# Auto_Final_v2_0.net
KiCad netlist of a schematic drawn in EAGLE
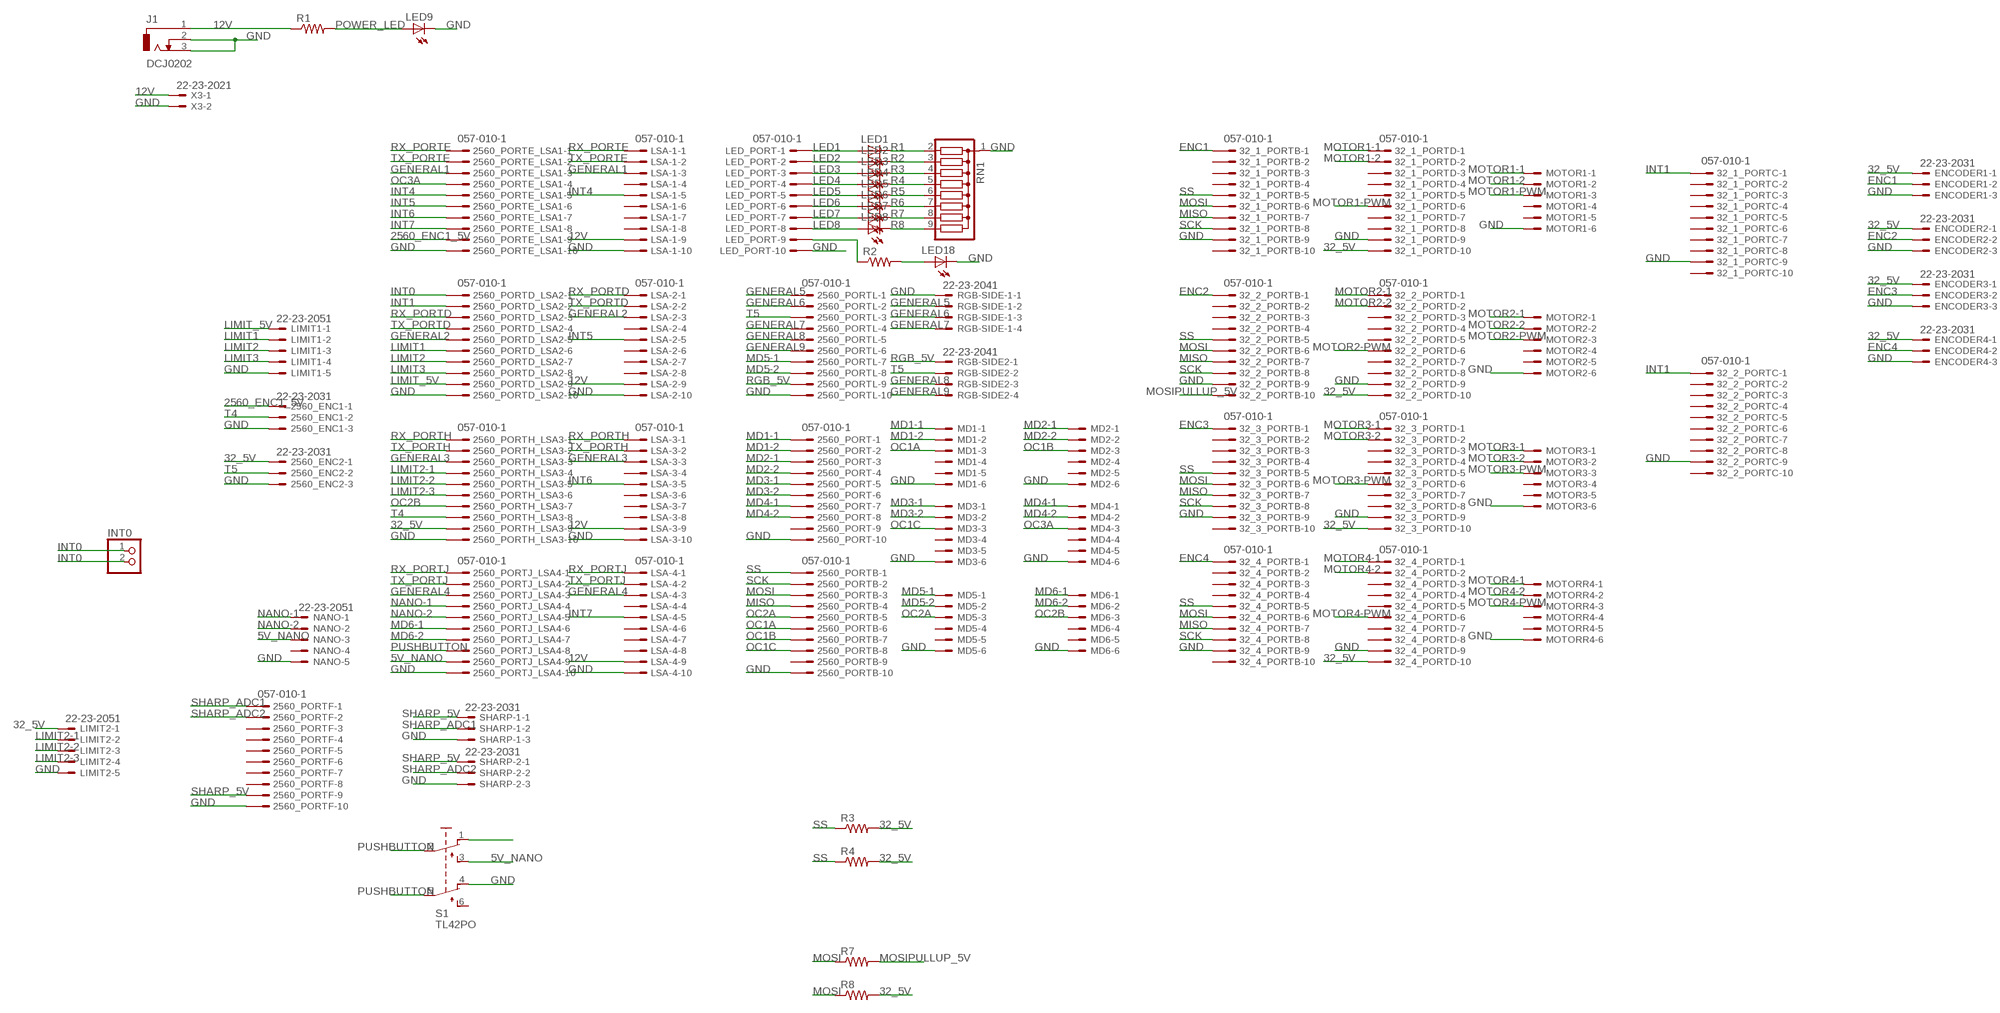
[diagram p0: schematic, sheet 1]

(export (version "E")
  (design (tool "Eeschema 10.0.6"))
  (components
    (comp (ref "32_1_PORTB")
      (value "057-010-1")
      (footprint "eagle-import:057-010-1")
      (libsource (lib "eagle-import") (part "057-010-1"))
    )
    (comp (ref "32_1_PORTC")
      (value "057-010-1")
      (footprint "eagle-import:057-010-1")
      (libsource (lib "eagle-import") (part "057-010-1"))
    )
    (comp (ref "32_1_PORTD")
      (value "057-010-1")
      (footprint "eagle-import:057-010-1")
      (libsource (lib "eagle-import") (part "057-010-1"))
    )
    (comp (ref "32_2_PORTB")
      (value "057-010-1")
      (footprint "eagle-import:057-010-1")
      (libsource (lib "eagle-import") (part "057-010-1"))
    )
    (comp (ref "32_2_PORTC")
      (value "057-010-1")
      (footprint "eagle-import:057-010-1")
      (libsource (lib "eagle-import") (part "057-010-1"))
    )
    (comp (ref "32_2_PORTD")
      (value "057-010-1")
      (footprint "eagle-import:057-010-1")
      (libsource (lib "eagle-import") (part "057-010-1"))
    )
    (comp (ref "32_3_PORTB")
      (value "057-010-1")
      (footprint "eagle-import:057-010-1")
      (libsource (lib "eagle-import") (part "057-010-1"))
    )
    (comp (ref "32_3_PORTD")
      (value "057-010-1")
      (footprint "eagle-import:057-010-1")
      (libsource (lib "eagle-import") (part "057-010-1"))
    )
    (comp (ref "32_4_PORTB")
      (value "057-010-1")
      (footprint "eagle-import:057-010-1")
      (libsource (lib "eagle-import") (part "057-010-1"))
    )
    (comp (ref "32_4_PORTD")
      (value "057-010-1")
      (footprint "eagle-import:057-010-1")
      (libsource (lib "eagle-import") (part "057-010-1"))
    )
    (comp (ref "2560_ENC1")
      (value "22-23-2031")
      (footprint "eagle-import:22-23-2031")
      (fields (field (name "MF") "MOLEX"))
      (libsource (lib "eagle-import") (part "22-23-2031"))
    )
    (comp (ref "2560_ENC2")
      (value "22-23-2031")
      (footprint "eagle-import:22-23-2031")
      (fields (field (name "MF") "MOLEX"))
      (libsource (lib "eagle-import") (part "22-23-2031"))
    )
    (comp (ref "2560_PORT")
      (value "057-010-1")
      (footprint "eagle-import:057-010-1")
      (libsource (lib "eagle-import") (part "057-010-1"))
    )
    (comp (ref "2560_PORTB")
      (value "057-010-1")
      (footprint "eagle-import:057-010-1")
      (libsource (lib "eagle-import") (part "057-010-1"))
    )
    (comp (ref "2560_PORTD_LSA2")
      (value "057-010-1")
      (footprint "eagle-import:057-010-1")
      (libsource (lib "eagle-import") (part "057-010-1"))
    )
    (comp (ref "2560_PORTE_LSA1")
      (value "057-010-1")
      (footprint "eagle-import:057-010-1")
      (libsource (lib "eagle-import") (part "057-010-1"))
    )
    (comp (ref "2560_PORTF")
      (value "057-010-1")
      (footprint "eagle-import:057-010-1")
      (libsource (lib "eagle-import") (part "057-010-1"))
    )
    (comp (ref "2560_PORTH_LSA3")
      (value "057-010-1")
      (footprint "eagle-import:057-010-1")
      (libsource (lib "eagle-import") (part "057-010-1"))
    )
    (comp (ref "2560_PORTJ_LSA4")
      (value "057-010-1")
      (footprint "eagle-import:057-010-1")
      (libsource (lib "eagle-import") (part "057-010-1"))
    )
    (comp (ref "2560_PORTL")
      (value "057-010-1")
      (footprint "eagle-import:057-010-1")
      (libsource (lib "eagle-import") (part "057-010-1"))
    )
    (comp (ref "ENCODER1")
      (value "22-23-2031")
      (footprint "eagle-import:22-23-2031")
      (fields (field (name "MF") "MOLEX"))
      (libsource (lib "eagle-import") (part "22-23-2031"))
    )
    (comp (ref "ENCODER2")
      (value "22-23-2031")
      (footprint "eagle-import:22-23-2031")
      (fields (field (name "MF") "MOLEX"))
      (libsource (lib "eagle-import") (part "22-23-2031"))
    )
    (comp (ref "ENCODER3")
      (value "22-23-2031")
      (footprint "eagle-import:22-23-2031")
      (fields (field (name "MF") "MOLEX"))
      (libsource (lib "eagle-import") (part "22-23-2031"))
    )
    (comp (ref "ENCODER4")
      (value "22-23-2031")
      (footprint "eagle-import:22-23-2031")
      (fields (field (name "MF") "MOLEX"))
      (libsource (lib "eagle-import") (part "22-23-2031"))
    )
    (comp (ref "INT0")
      (value "PINHD-1X2")
      (footprint "eagle-import:1X02")
      (libsource (lib "eagle-import") (part "PINHD-1X2"))
    )
    (comp (ref "J1")
      (value "DCJ0202")
      (footprint "eagle-import:DCJ0202")
      (libsource (lib "eagle-import") (part "DCJ0202"))
    )
    (comp (ref "LED1")
      (value "LED3MM")
      (footprint "eagle-import:LED3MM")
      (libsource (lib "eagle-import") (part "LED3MM"))
    )
    (comp (ref "LED2")
      (value "LED3MM")
      (footprint "eagle-import:LED3MM")
      (libsource (lib "eagle-import") (part "LED3MM"))
    )
    (comp (ref "LED3")
      (value "LED3MM")
      (footprint "eagle-import:LED3MM")
      (libsource (lib "eagle-import") (part "LED3MM"))
    )
    (comp (ref "LED4")
      (value "LED3MM")
      (footprint "eagle-import:LED3MM")
      (libsource (lib "eagle-import") (part "LED3MM"))
    )
    (comp (ref "LED5")
      (value "LED3MM")
      (footprint "eagle-import:LED3MM")
      (libsource (lib "eagle-import") (part "LED3MM"))
    )
    (comp (ref "LED6")
      (value "LED3MM")
      (footprint "eagle-import:LED3MM")
      (libsource (lib "eagle-import") (part "LED3MM"))
    )
    (comp (ref "LED7")
      (value "LED3MM")
      (footprint "eagle-import:LED3MM")
      (libsource (lib "eagle-import") (part "LED3MM"))
    )
    (comp (ref "LED8")
      (value "LED3MM")
      (footprint "eagle-import:LED3MM")
      (libsource (lib "eagle-import") (part "LED3MM"))
    )
    (comp (ref "LED9")
      (value "LED5MM")
      (footprint "eagle-import:LED5MM")
      (libsource (lib "eagle-import") (part "LED5MM"))
    )
    (comp (ref "LED18")
      (value "LED3MM")
      (footprint "eagle-import:LED3MM")
      (libsource (lib "eagle-import") (part "LED3MM"))
    )
    (comp (ref "LED_PORT")
      (value "057-010-1")
      (footprint "eagle-import:057-010-1")
      (libsource (lib "eagle-import") (part "057-010-1"))
    )
    (comp (ref "LIMIT1")
      (value "22-23-2051")
      (footprint "eagle-import:22-23-2051")
      (fields (field (name "MF") "MOLEX"))
      (libsource (lib "eagle-import") (part "22-23-2051"))
    )
    (comp (ref "LIMIT2")
      (value "22-23-2051")
      (footprint "eagle-import:22-23-2051")
      (fields (field (name "MF") "MOLEX"))
      (libsource (lib "eagle-import") (part "22-23-2051"))
    )
    (comp (ref "LSA-1")
      (value "057-010-1")
      (footprint "eagle-import:057-010-1")
      (libsource (lib "eagle-import") (part "057-010-1"))
    )
    (comp (ref "LSA-2")
      (value "057-010-1")
      (footprint "eagle-import:057-010-1")
      (libsource (lib "eagle-import") (part "057-010-1"))
    )
    (comp (ref "LSA-3")
      (value "057-010-1")
      (footprint "eagle-import:057-010-1")
      (libsource (lib "eagle-import") (part "057-010-1"))
    )
    (comp (ref "LSA-4")
      (value "057-010-1")
      (footprint "eagle-import:057-010-1")
      (libsource (lib "eagle-import") (part "057-010-1"))
    )
    (comp (ref "MD1")
      (value "22-23-2061")
      (footprint "eagle-import:22-23-2061")
      (fields (field (name "MF") "MOLEX"))
      (libsource (lib "eagle-import") (part "22-23-2061"))
    )
    (comp (ref "MD2")
      (value "22-23-2061")
      (footprint "eagle-import:22-23-2061")
      (fields (field (name "MF") "MOLEX"))
      (libsource (lib "eagle-import") (part "22-23-2061"))
    )
    (comp (ref "MD3")
      (value "22-23-2061")
      (footprint "eagle-import:22-23-2061")
      (fields (field (name "MF") "MOLEX"))
      (libsource (lib "eagle-import") (part "22-23-2061"))
    )
    (comp (ref "MD4")
      (value "22-23-2061")
      (footprint "eagle-import:22-23-2061")
      (fields (field (name "MF") "MOLEX"))
      (libsource (lib "eagle-import") (part "22-23-2061"))
    )
    (comp (ref "MD5")
      (value "22-23-2061")
      (footprint "eagle-import:22-23-2061")
      (fields (field (name "MF") "MOLEX"))
      (libsource (lib "eagle-import") (part "22-23-2061"))
    )
    (comp (ref "MD6")
      (value "22-23-2061")
      (footprint "eagle-import:22-23-2061")
      (fields (field (name "MF") "MOLEX"))
      (libsource (lib "eagle-import") (part "22-23-2061"))
    )
    (comp (ref "MOTOR1")
      (value "22-23-2061")
      (footprint "eagle-import:22-23-2061")
      (fields (field (name "MF") "MOLEX"))
      (libsource (lib "eagle-import") (part "22-23-2061"))
    )
    (comp (ref "MOTOR2")
      (value "22-23-2061")
      (footprint "eagle-import:22-23-2061")
      (fields (field (name "MF") "MOLEX"))
      (libsource (lib "eagle-import") (part "22-23-2061"))
    )
    (comp (ref "MOTOR3")
      (value "22-23-2061")
      (footprint "eagle-import:22-23-2061")
      (fields (field (name "MF") "MOLEX"))
      (libsource (lib "eagle-import") (part "22-23-2061"))
    )
    (comp (ref "MOTORR4")
      (value "22-23-2061")
      (footprint "eagle-import:22-23-2061")
      (fields (field (name "MF") "MOLEX"))
      (libsource (lib "eagle-import") (part "22-23-2061"))
    )
    (comp (ref "NANO")
      (value "22-23-2051")
      (footprint "eagle-import:22-23-2051")
      (fields (field (name "MF") "MOLEX"))
      (libsource (lib "eagle-import") (part "22-23-2051"))
    )
    (comp (ref "R1")
      (value "R-US_0204/7")
      (footprint "eagle-import:0204_7")
      (libsource (lib "eagle-import") (part "R-US_0204/7"))
    )
    (comp (ref "R2")
      (value "R-US_0204/7")
      (footprint "eagle-import:0204_7")
      (libsource (lib "eagle-import") (part "R-US_0204/7"))
    )
    (comp (ref "R3")
      (value "R-US_0204/7")
      (footprint "eagle-import:0204_7")
      (libsource (lib "eagle-import") (part "R-US_0204/7"))
    )
    (comp (ref "R4")
      (value "R-US_0204/7")
      (footprint "eagle-import:0204_7")
      (libsource (lib "eagle-import") (part "R-US_0204/7"))
    )
    (comp (ref "R7")
      (value "R-US_0204/7")
      (footprint "eagle-import:0204_7")
      (libsource (lib "eagle-import") (part "R-US_0204/7"))
    )
    (comp (ref "R8")
      (value "R-US_0204/7")
      (footprint "eagle-import:0204_7")
      (libsource (lib "eagle-import") (part "R-US_0204/7"))
    )
    (comp (ref "RGB-SIDE-1")
      (value "22-23-2041")
      (footprint "eagle-import:22-23-2041")
      (fields (field (name "MF") "MOLEX"))
      (libsource (lib "eagle-import") (part "22-23-2041"))
    )
    (comp (ref "RGB-SIDE2")
      (value "22-23-2041")
      (footprint "eagle-import:22-23-2041")
      (fields (field (name "MF") "MOLEX"))
      (libsource (lib "eagle-import") (part "22-23-2041"))
    )
    (comp (ref "RN1")
      (value "G08R")
      (footprint "eagle-import:SIL9")
      (libsource (lib "eagle-import") (part "G08R"))
    )
    (comp (ref "S1")
      (value "TL42PO")
      (footprint "eagle-import:TL4XPO")
      (libsource (lib "eagle-import") (part "TL42PO"))
    )
    (comp (ref "SHARP-1")
      (value "22-23-2031")
      (footprint "eagle-import:22-23-2031")
      (fields (field (name "MF") "MOLEX"))
      (libsource (lib "eagle-import") (part "22-23-2031"))
    )
    (comp (ref "SHARP-2")
      (value "22-23-2031")
      (footprint "eagle-import:22-23-2031")
      (fields (field (name "MF") "MOLEX"))
      (libsource (lib "eagle-import") (part "22-23-2031"))
    )
    (comp (ref "X3")
      (value "22-23-2021")
      (footprint "eagle-import:22-23-2021")
      (fields (field (name "MF") "MOLEX"))
      (libsource (lib "eagle-import") (part "22-23-2021"))
    )
  )
  (nets
    (net (code "1") (name "/5V_NANO") (class "Default")
      (node (ref "2560_PORTJ_LSA4") (pin "9") (pinfunction "S_9") (pintype "passive"))
      (node (ref "NANO") (pin "3") (pinfunction "S_3") (pintype "passive"))
      (node (ref "S1") (pin "3") (pinfunction "S_3") (pintype "passive"))
    )
    (net (code "2") (name "/12V") (class "Default")
      (node (ref "J1") (pin "1") (pinfunction "1_1") (pintype "passive"))
      (node (ref "LSA-1") (pin "9") (pinfunction "S_9") (pintype "passive"))
      (node (ref "LSA-2") (pin "9") (pinfunction "S_9") (pintype "passive"))
      (node (ref "LSA-3") (pin "9") (pinfunction "S_9") (pintype "passive"))
      (node (ref "LSA-4") (pin "9") (pinfunction "S_9") (pintype "passive"))
      (node (ref "R1") (pin "1") (pinfunction "1_1") (pintype "passive"))
      (node (ref "X3") (pin "1") (pinfunction "S_1") (pintype "passive"))
    )
    (net (code "3") (name "/32_5V") (class "Default")
      (node (ref "2560_ENC2") (pin "1") (pinfunction "S_1") (pintype "passive"))
      (node (ref "2560_PORTH_LSA3") (pin "9") (pinfunction "S_9") (pintype "passive"))
      (node (ref "32_1_PORTD") (pin "10") (pinfunction "S_10") (pintype "passive"))
      (node (ref "32_2_PORTD") (pin "10") (pinfunction "S_10") (pintype "passive"))
      (node (ref "32_3_PORTD") (pin "10") (pinfunction "S_10") (pintype "passive"))
      (node (ref "32_4_PORTD") (pin "10") (pinfunction "S_10") (pintype "passive"))
      (node (ref "ENCODER1") (pin "1") (pinfunction "S_1") (pintype "passive"))
      (node (ref "ENCODER2") (pin "1") (pinfunction "S_1") (pintype "passive"))
      (node (ref "ENCODER3") (pin "1") (pinfunction "S_1") (pintype "passive"))
      (node (ref "ENCODER4") (pin "1") (pinfunction "S_1") (pintype "passive"))
      (node (ref "LIMIT2") (pin "1") (pinfunction "S_1") (pintype "passive"))
      (node (ref "R3") (pin "2") (pinfunction "2_2") (pintype "passive"))
      (node (ref "R4") (pin "2") (pinfunction "2_2") (pintype "passive"))
      (node (ref "R8") (pin "2") (pinfunction "2_2") (pintype "passive"))
    )
    (net (code "4") (name "/2560_ENC1_5V") (class "Default")
      (node (ref "2560_ENC1") (pin "1") (pinfunction "S_1") (pintype "passive"))
      (node (ref "2560_PORTE_LSA1") (pin "9") (pinfunction "S_9") (pintype "passive"))
    )
    (net (code "5") (name "/ENC1") (class "Default")
      (node (ref "32_1_PORTB") (pin "1") (pinfunction "S_1") (pintype "passive"))
      (node (ref "ENCODER1") (pin "2") (pinfunction "S_2") (pintype "passive"))
    )
    (net (code "6") (name "/ENC2") (class "Default")
      (node (ref "32_2_PORTB") (pin "1") (pinfunction "S_1") (pintype "passive"))
      (node (ref "ENCODER2") (pin "2") (pinfunction "S_2") (pintype "passive"))
    )
    (net (code "7") (name "/ENC3") (class "Default")
      (node (ref "32_3_PORTB") (pin "1") (pinfunction "S_1") (pintype "passive"))
      (node (ref "ENCODER3") (pin "2") (pinfunction "S_2") (pintype "passive"))
    )
    (net (code "8") (name "/ENC4") (class "Default")
      (node (ref "32_4_PORTB") (pin "1") (pinfunction "S_1") (pintype "passive"))
      (node (ref "ENCODER4") (pin "2") (pinfunction "S_2") (pintype "passive"))
    )
    (net (code "9") (name "/GENERAL1") (class "Default")
      (node (ref "2560_PORTE_LSA1") (pin "3") (pinfunction "S_3") (pintype "passive"))
      (node (ref "LSA-1") (pin "3") (pinfunction "S_3") (pintype "passive"))
    )
    (net (code "10") (name "/GENERAL2") (class "Default")
      (node (ref "2560_PORTD_LSA2") (pin "5") (pinfunction "S_5") (pintype "passive"))
      (node (ref "LSA-2") (pin "3") (pinfunction "S_3") (pintype "passive"))
    )
    (net (code "11") (name "/GENERAL3") (class "Default")
      (node (ref "2560_PORTH_LSA3") (pin "3") (pinfunction "S_3") (pintype "passive"))
      (node (ref "LSA-3") (pin "3") (pinfunction "S_3") (pintype "passive"))
    )
    (net (code "12") (name "/GENERAL4") (class "Default")
      (node (ref "2560_PORTJ_LSA4") (pin "3") (pinfunction "S_3") (pintype "passive"))
      (node (ref "LSA-4") (pin "3") (pinfunction "S_3") (pintype "passive"))
    )
    (net (code "13") (name "/GENERAL5") (class "Default")
      (node (ref "2560_PORTL") (pin "1") (pinfunction "S_1") (pintype "passive"))
      (node (ref "RGB-SIDE-1") (pin "2") (pinfunction "S_2") (pintype "passive"))
    )
    (net (code "14") (name "/GENERAL6") (class "Default")
      (node (ref "2560_PORTL") (pin "2") (pinfunction "S_2") (pintype "passive"))
      (node (ref "RGB-SIDE-1") (pin "3") (pinfunction "S_3") (pintype "passive"))
    )
    (net (code "15") (name "/GENERAL7") (class "Default")
      (node (ref "2560_PORTL") (pin "4") (pinfunction "S_4") (pintype "passive"))
      (node (ref "RGB-SIDE-1") (pin "4") (pinfunction "S_4") (pintype "passive"))
    )
    (net (code "16") (name "/GENERAL8") (class "Default")
      (node (ref "2560_PORTL") (pin "5") (pinfunction "S_5") (pintype "passive"))
      (node (ref "RGB-SIDE2") (pin "3") (pinfunction "S_3") (pintype "passive"))
    )
    (net (code "17") (name "/GENERAL9") (class "Default")
      (node (ref "2560_PORTL") (pin "6") (pinfunction "S_6") (pintype "passive"))
      (node (ref "RGB-SIDE2") (pin "4") (pinfunction "S_4") (pintype "passive"))
    )
    (net (code "18") (name "/GND") (class "Default")
      (node (ref "2560_ENC1") (pin "3") (pinfunction "S_3") (pintype "passive"))
      (node (ref "2560_ENC2") (pin "3") (pinfunction "S_3") (pintype "passive"))
      (node (ref "2560_PORT") (pin "10") (pinfunction "S_10") (pintype "passive"))
      (node (ref "2560_PORTB") (pin "10") (pinfunction "S_10") (pintype "passive"))
      (node (ref "2560_PORTD_LSA2") (pin "10") (pinfunction "S_10") (pintype "passive"))
      (node (ref "2560_PORTE_LSA1") (pin "10") (pinfunction "S_10") (pintype "passive"))
      (node (ref "2560_PORTF") (pin "10") (pinfunction "S_10") (pintype "passive"))
      (node (ref "2560_PORTH_LSA3") (pin "10") (pinfunction "S_10") (pintype "passive"))
      (node (ref "2560_PORTJ_LSA4") (pin "10") (pinfunction "S_10") (pintype "passive"))
      (node (ref "2560_PORTL") (pin "10") (pinfunction "S_10") (pintype "passive"))
      (node (ref "32_1_PORTB") (pin "9") (pinfunction "S_9") (pintype "passive"))
      (node (ref "32_1_PORTC") (pin "9") (pinfunction "S_9") (pintype "passive"))
      (node (ref "32_1_PORTD") (pin "9") (pinfunction "S_9") (pintype "passive"))
      (node (ref "32_2_PORTB") (pin "9") (pinfunction "S_9") (pintype "passive"))
      (node (ref "32_2_PORTC") (pin "9") (pinfunction "S_9") (pintype "passive"))
      (node (ref "32_2_PORTD") (pin "9") (pinfunction "S_9") (pintype "passive"))
      (node (ref "32_3_PORTB") (pin "9") (pinfunction "S_9") (pintype "passive"))
      (node (ref "32_3_PORTD") (pin "9") (pinfunction "S_9") (pintype "passive"))
      (node (ref "32_4_PORTB") (pin "9") (pinfunction "S_9") (pintype "passive"))
      (node (ref "32_4_PORTD") (pin "9") (pinfunction "S_9") (pintype "passive"))
      (node (ref "ENCODER1") (pin "3") (pinfunction "S_3") (pintype "passive"))
      (node (ref "ENCODER2") (pin "3") (pinfunction "S_3") (pintype "passive"))
      (node (ref "ENCODER3") (pin "3") (pinfunction "S_3") (pintype "passive"))
      (node (ref "ENCODER4") (pin "3") (pinfunction "S_3") (pintype "passive"))
      (node (ref "J1") (pin "2") (pinfunction "2_2") (pintype "passive"))
      (node (ref "J1") (pin "3") (pinfunction "3_3") (pintype "passive"))
      (node (ref "LED18") (pin "K") (pinfunction "C_K") (pintype "passive"))
      (node (ref "LED9") (pin "K") (pinfunction "C_K") (pintype "passive"))
      (node (ref "LED_PORT") (pin "10") (pinfunction "S_10") (pintype "passive"))
      (node (ref "LIMIT1") (pin "5") (pinfunction "S_5") (pintype "passive"))
      (node (ref "LIMIT2") (pin "5") (pinfunction "S_5") (pintype "passive"))
      (node (ref "LSA-1") (pin "10") (pinfunction "S_10") (pintype "passive"))
      (node (ref "LSA-2") (pin "10") (pinfunction "S_10") (pintype "passive"))
      (node (ref "LSA-3") (pin "10") (pinfunction "S_10") (pintype "passive"))
      (node (ref "LSA-4") (pin "10") (pinfunction "S_10") (pintype "passive"))
      (node (ref "MD1") (pin "6") (pinfunction "S_6") (pintype "passive"))
      (node (ref "MD2") (pin "6") (pinfunction "S_6") (pintype "passive"))
      (node (ref "MD3") (pin "6") (pinfunction "S_6") (pintype "passive"))
      (node (ref "MD4") (pin "6") (pinfunction "S_6") (pintype "passive"))
      (node (ref "MD5") (pin "6") (pinfunction "S_6") (pintype "passive"))
      (node (ref "MD6") (pin "6") (pinfunction "S_6") (pintype "passive"))
      (node (ref "MOTOR1") (pin "6") (pinfunction "S_6") (pintype "passive"))
      (node (ref "MOTOR2") (pin "6") (pinfunction "S_6") (pintype "passive"))
      (node (ref "MOTOR3") (pin "6") (pinfunction "S_6") (pintype "passive"))
      (node (ref "MOTORR4") (pin "6") (pinfunction "S_6") (pintype "passive"))
      (node (ref "NANO") (pin "5") (pinfunction "S_5") (pintype "passive"))
      (node (ref "RGB-SIDE-1") (pin "1") (pinfunction "S_1") (pintype "passive"))
      (node (ref "RN1") (pin "1") (pinfunction "1_1") (pintype "passive"))
      (node (ref "S1") (pin "4") (pinfunction "O1_4") (pintype "passive"))
      (node (ref "SHARP-1") (pin "3") (pinfunction "S_3") (pintype "passive"))
      (node (ref "SHARP-2") (pin "3") (pinfunction "S_3") (pintype "passive"))
      (node (ref "X3") (pin "2") (pinfunction "S_2") (pintype "passive"))
    )
    (net (code "19") (name "/INT0") (class "Default")
      (node (ref "2560_PORTD_LSA2") (pin "1") (pinfunction "S_1") (pintype "passive"))
      (node (ref "INT0") (pin "1") (pinfunction "1_1") (pintype "passive"))
      (node (ref "INT0") (pin "2") (pinfunction "2_2") (pintype "passive"))
    )
    (net (code "20") (name "/INT1") (class "Default")
      (node (ref "2560_PORTD_LSA2") (pin "2") (pinfunction "S_2") (pintype "passive"))
      (node (ref "32_1_PORTC") (pin "1") (pinfunction "S_1") (pintype "passive"))
      (node (ref "32_2_PORTC") (pin "1") (pinfunction "S_1") (pintype "passive"))
    )
    (net (code "21") (name "/INT4") (class "Default")
      (node (ref "2560_PORTE_LSA1") (pin "5") (pinfunction "S_5") (pintype "passive"))
      (node (ref "LSA-1") (pin "5") (pinfunction "S_5") (pintype "passive"))
    )
    (net (code "22") (name "/INT5") (class "Default")
      (node (ref "2560_PORTE_LSA1") (pin "6") (pinfunction "S_6") (pintype "passive"))
      (node (ref "LSA-2") (pin "5") (pinfunction "S_5") (pintype "passive"))
    )
    (net (code "23") (name "/INT6") (class "Default")
      (node (ref "2560_PORTE_LSA1") (pin "7") (pinfunction "S_7") (pintype "passive"))
      (node (ref "LSA-3") (pin "5") (pinfunction "S_5") (pintype "passive"))
    )
    (net (code "24") (name "/INT7") (class "Default")
      (node (ref "2560_PORTE_LSA1") (pin "8") (pinfunction "S_8") (pintype "passive"))
      (node (ref "LSA-4") (pin "5") (pinfunction "S_5") (pintype "passive"))
    )
    (net (code "25") (name "/LED1") (class "Default")
      (node (ref "LED1") (pin "A") (pinfunction "A_A") (pintype "passive"))
      (node (ref "LED_PORT") (pin "1") (pinfunction "S_1") (pintype "passive"))
    )
    (net (code "26") (name "/LED2") (class "Default")
      (node (ref "LED2") (pin "A") (pinfunction "A_A") (pintype "passive"))
      (node (ref "LED_PORT") (pin "2") (pinfunction "S_2") (pintype "passive"))
    )
    (net (code "27") (name "/LED3") (class "Default")
      (node (ref "LED3") (pin "A") (pinfunction "A_A") (pintype "passive"))
      (node (ref "LED_PORT") (pin "3") (pinfunction "S_3") (pintype "passive"))
    )
    (net (code "28") (name "/LED4") (class "Default")
      (node (ref "LED4") (pin "A") (pinfunction "A_A") (pintype "passive"))
      (node (ref "LED_PORT") (pin "4") (pinfunction "S_4") (pintype "passive"))
    )
    (net (code "29") (name "/LED5") (class "Default")
      (node (ref "LED5") (pin "A") (pinfunction "A_A") (pintype "passive"))
      (node (ref "LED_PORT") (pin "5") (pinfunction "S_5") (pintype "passive"))
    )
    (net (code "30") (name "/LED6") (class "Default")
      (node (ref "LED6") (pin "A") (pinfunction "A_A") (pintype "passive"))
      (node (ref "LED_PORT") (pin "6") (pinfunction "S_6") (pintype "passive"))
    )
    (net (code "31") (name "/LED7") (class "Default")
      (node (ref "LED7") (pin "A") (pinfunction "A_A") (pintype "passive"))
      (node (ref "LED_PORT") (pin "7") (pinfunction "S_7") (pintype "passive"))
    )
    (net (code "32") (name "/LED8") (class "Default")
      (node (ref "LED8") (pin "A") (pinfunction "A_A") (pintype "passive"))
      (node (ref "LED_PORT") (pin "8") (pinfunction "S_8") (pintype "passive"))
    )
    (net (code "33") (name "/LIMIT1") (class "Default")
      (node (ref "2560_PORTD_LSA2") (pin "6") (pinfunction "S_6") (pintype "passive"))
      (node (ref "LIMIT1") (pin "2") (pinfunction "S_2") (pintype "passive"))
    )
    (net (code "34") (name "/LIMIT2") (class "Default")
      (node (ref "2560_PORTD_LSA2") (pin "7") (pinfunction "S_7") (pintype "passive"))
      (node (ref "LIMIT1") (pin "3") (pinfunction "S_3") (pintype "passive"))
    )
    (net (code "35") (name "/LIMIT2-1") (class "Default")
      (node (ref "2560_PORTH_LSA3") (pin "4") (pinfunction "S_4") (pintype "passive"))
      (node (ref "LIMIT2") (pin "2") (pinfunction "S_2") (pintype "passive"))
    )
    (net (code "36") (name "/LIMIT2-2") (class "Default")
      (node (ref "2560_PORTH_LSA3") (pin "5") (pinfunction "S_5") (pintype "passive"))
      (node (ref "LIMIT2") (pin "3") (pinfunction "S_3") (pintype "passive"))
    )
    (net (code "37") (name "/LIMIT2-3") (class "Default")
      (node (ref "2560_PORTH_LSA3") (pin "6") (pinfunction "S_6") (pintype "passive"))
      (node (ref "LIMIT2") (pin "4") (pinfunction "S_4") (pintype "passive"))
    )
    (net (code "38") (name "/LIMIT3") (class "Default")
      (node (ref "2560_PORTD_LSA2") (pin "8") (pinfunction "S_8") (pintype "passive"))
      (node (ref "LIMIT1") (pin "4") (pinfunction "S_4") (pintype "passive"))
    )
    (net (code "39") (name "/LIMIT_5V") (class "Default")
      (node (ref "2560_PORTD_LSA2") (pin "9") (pinfunction "S_9") (pintype "passive"))
      (node (ref "LIMIT1") (pin "1") (pinfunction "S_1") (pintype "passive"))
    )
    (net (code "40") (name "/MD1-1") (class "Default")
      (node (ref "2560_PORT") (pin "1") (pinfunction "S_1") (pintype "passive"))
      (node (ref "MD1") (pin "1") (pinfunction "S_1") (pintype "passive"))
    )
    (net (code "41") (name "/MD1-2") (class "Default")
      (node (ref "2560_PORT") (pin "2") (pinfunction "S_2") (pintype "passive"))
      (node (ref "MD1") (pin "2") (pinfunction "S_2") (pintype "passive"))
    )
    (net (code "42") (name "/MD2-1") (class "Default")
      (node (ref "2560_PORT") (pin "3") (pinfunction "S_3") (pintype "passive"))
      (node (ref "MD2") (pin "1") (pinfunction "S_1") (pintype "passive"))
    )
    (net (code "43") (name "/MD2-2") (class "Default")
      (node (ref "2560_PORT") (pin "4") (pinfunction "S_4") (pintype "passive"))
      (node (ref "MD2") (pin "2") (pinfunction "S_2") (pintype "passive"))
    )
    (net (code "44") (name "/MD3-1") (class "Default")
      (node (ref "2560_PORT") (pin "5") (pinfunction "S_5") (pintype "passive"))
      (node (ref "MD3") (pin "1") (pinfunction "S_1") (pintype "passive"))
    )
    (net (code "45") (name "/MD3-2") (class "Default")
      (node (ref "2560_PORT") (pin "6") (pinfunction "S_6") (pintype "passive"))
      (node (ref "MD3") (pin "2") (pinfunction "S_2") (pintype "passive"))
    )
    (net (code "46") (name "/MD4-1") (class "Default")
      (node (ref "2560_PORT") (pin "7") (pinfunction "S_7") (pintype "passive"))
      (node (ref "MD4") (pin "1") (pinfunction "S_1") (pintype "passive"))
    )
    (net (code "47") (name "/MD4-2") (class "Default")
      (node (ref "2560_PORT") (pin "8") (pinfunction "S_8") (pintype "passive"))
      (node (ref "MD4") (pin "2") (pinfunction "S_2") (pintype "passive"))
    )
    (net (code "48") (name "/MD5-1") (class "Default")
      (node (ref "2560_PORTL") (pin "7") (pinfunction "S_7") (pintype "passive"))
      (node (ref "MD5") (pin "1") (pinfunction "S_1") (pintype "passive"))
    )
    (net (code "49") (name "/MD5-2") (class "Default")
      (node (ref "2560_PORTL") (pin "8") (pinfunction "S_8") (pintype "passive"))
      (node (ref "MD5") (pin "2") (pinfunction "S_2") (pintype "passive"))
    )
    (net (code "50") (name "/MD6-1") (class "Default")
      (node (ref "2560_PORTJ_LSA4") (pin "6") (pinfunction "S_6") (pintype "passive"))
      (node (ref "MD6") (pin "1") (pinfunction "S_1") (pintype "passive"))
    )
    (net (code "51") (name "/MD6-2") (class "Default")
      (node (ref "2560_PORTJ_LSA4") (pin "7") (pinfunction "S_7") (pintype "passive"))
      (node (ref "MD6") (pin "2") (pinfunction "S_2") (pintype "passive"))
    )
    (net (code "52") (name "/MISO") (class "Default")
      (node (ref "2560_PORTB") (pin "4") (pinfunction "S_4") (pintype "passive"))
      (node (ref "32_1_PORTB") (pin "7") (pinfunction "S_7") (pintype "passive"))
      (node (ref "32_2_PORTB") (pin "7") (pinfunction "S_7") (pintype "passive"))
      (node (ref "32_3_PORTB") (pin "7") (pinfunction "S_7") (pintype "passive"))
      (node (ref "32_4_PORTB") (pin "7") (pinfunction "S_7") (pintype "passive"))
    )
    (net (code "53") (name "/MOSI") (class "Default")
      (node (ref "2560_PORTB") (pin "3") (pinfunction "S_3") (pintype "passive"))
      (node (ref "32_1_PORTB") (pin "6") (pinfunction "S_6") (pintype "passive"))
      (node (ref "32_2_PORTB") (pin "6") (pinfunction "S_6") (pintype "passive"))
      (node (ref "32_3_PORTB") (pin "6") (pinfunction "S_6") (pintype "passive"))
      (node (ref "32_4_PORTB") (pin "6") (pinfunction "S_6") (pintype "passive"))
      (node (ref "R7") (pin "1") (pinfunction "1_1") (pintype "passive"))
      (node (ref "R8") (pin "1") (pinfunction "1_1") (pintype "passive"))
    )
    (net (code "54") (name "/MOSIPULLUP_5V") (class "Default")
      (node (ref "32_2_PORTB") (pin "10") (pinfunction "S_10") (pintype "passive"))
      (node (ref "R7") (pin "2") (pinfunction "2_2") (pintype "passive"))
    )
    (net (code "55") (name "/MOTOR1-1") (class "Default")
      (node (ref "32_1_PORTD") (pin "1") (pinfunction "S_1") (pintype "passive"))
      (node (ref "MOTOR1") (pin "1") (pinfunction "S_1") (pintype "passive"))
    )
    (net (code "56") (name "/MOTOR1-2") (class "Default")
      (node (ref "32_1_PORTD") (pin "2") (pinfunction "S_2") (pintype "passive"))
      (node (ref "MOTOR1") (pin "2") (pinfunction "S_2") (pintype "passive"))
    )
    (net (code "57") (name "/MOTOR1-PWM") (class "Default")
      (node (ref "32_1_PORTD") (pin "6") (pinfunction "S_6") (pintype "passive"))
      (node (ref "MOTOR1") (pin "3") (pinfunction "S_3") (pintype "passive"))
    )
    (net (code "58") (name "/MOTOR2-1") (class "Default")
      (node (ref "32_2_PORTD") (pin "1") (pinfunction "S_1") (pintype "passive"))
      (node (ref "MOTOR2") (pin "1") (pinfunction "S_1") (pintype "passive"))
    )
    (net (code "59") (name "/MOTOR2-2") (class "Default")
      (node (ref "32_2_PORTD") (pin "2") (pinfunction "S_2") (pintype "passive"))
      (node (ref "MOTOR2") (pin "2") (pinfunction "S_2") (pintype "passive"))
    )
    (net (code "60") (name "/MOTOR2-PWM") (class "Default")
      (node (ref "32_2_PORTD") (pin "6") (pinfunction "S_6") (pintype "passive"))
      (node (ref "MOTOR2") (pin "3") (pinfunction "S_3") (pintype "passive"))
    )
    (net (code "61") (name "/MOTOR3-1") (class "Default")
      (node (ref "32_3_PORTD") (pin "1") (pinfunction "S_1") (pintype "passive"))
      (node (ref "MOTOR3") (pin "1") (pinfunction "S_1") (pintype "passive"))
    )
    (net (code "62") (name "/MOTOR3-2") (class "Default")
      (node (ref "32_3_PORTD") (pin "2") (pinfunction "S_2") (pintype "passive"))
      (node (ref "MOTOR3") (pin "2") (pinfunction "S_2") (pintype "passive"))
    )
    (net (code "63") (name "/MOTOR3-PWM") (class "Default")
      (node (ref "32_3_PORTD") (pin "6") (pinfunction "S_6") (pintype "passive"))
      (node (ref "MOTOR3") (pin "3") (pinfunction "S_3") (pintype "passive"))
    )
    (net (code "64") (name "/MOTOR4-1") (class "Default")
      (node (ref "32_4_PORTD") (pin "1") (pinfunction "S_1") (pintype "passive"))
      (node (ref "MOTORR4") (pin "1") (pinfunction "S_1") (pintype "passive"))
    )
    (net (code "65") (name "/MOTOR4-2") (class "Default")
      (node (ref "32_4_PORTD") (pin "2") (pinfunction "S_2") (pintype "passive"))
      (node (ref "MOTORR4") (pin "2") (pinfunction "S_2") (pintype "passive"))
    )
    (net (code "66") (name "/MOTOR4-PWM") (class "Default")
      (node (ref "32_4_PORTD") (pin "6") (pinfunction "S_6") (pintype "passive"))
      (node (ref "MOTORR4") (pin "3") (pinfunction "S_3") (pintype "passive"))
    )
    (net (code "67") (name "/NANO-1") (class "Default")
      (node (ref "2560_PORTJ_LSA4") (pin "4") (pinfunction "S_4") (pintype "passive"))
      (node (ref "NANO") (pin "1") (pinfunction "S_1") (pintype "passive"))
    )
    (net (code "68") (name "/NANO-2") (class "Default")
      (node (ref "2560_PORTJ_LSA4") (pin "5") (pinfunction "S_5") (pintype "passive"))
      (node (ref "NANO") (pin "2") (pinfunction "S_2") (pintype "passive"))
    )
    (net (code "69") (name "/OC1A") (class "Default")
      (node (ref "2560_PORTB") (pin "6") (pinfunction "S_6") (pintype "passive"))
      (node (ref "MD1") (pin "3") (pinfunction "S_3") (pintype "passive"))
    )
    (net (code "70") (name "/OC1B") (class "Default")
      (node (ref "2560_PORTB") (pin "7") (pinfunction "S_7") (pintype "passive"))
      (node (ref "MD2") (pin "3") (pinfunction "S_3") (pintype "passive"))
    )
    (net (code "71") (name "/OC1C") (class "Default")
      (node (ref "2560_PORTB") (pin "8") (pinfunction "S_8") (pintype "passive"))
      (node (ref "MD3") (pin "3") (pinfunction "S_3") (pintype "passive"))
    )
    (net (code "72") (name "/OC2A") (class "Default")
      (node (ref "2560_PORTB") (pin "5") (pinfunction "S_5") (pintype "passive"))
      (node (ref "MD5") (pin "3") (pinfunction "S_3") (pintype "passive"))
    )
    (net (code "73") (name "/OC2B") (class "Default")
      (node (ref "2560_PORTH_LSA3") (pin "7") (pinfunction "S_7") (pintype "passive"))
      (node (ref "MD6") (pin "3") (pinfunction "S_3") (pintype "passive"))
    )
    (net (code "74") (name "/OC3A") (class "Default")
      (node (ref "2560_PORTE_LSA1") (pin "4") (pinfunction "S_4") (pintype "passive"))
      (node (ref "MD4") (pin "3") (pinfunction "S_3") (pintype "passive"))
    )
    (net (code "75") (name "/POWER_LED") (class "Default")
      (node (ref "LED9") (pin "A") (pinfunction "A_A") (pintype "passive"))
      (node (ref "R1") (pin "2") (pinfunction "2_2") (pintype "passive"))
    )
    (net (code "76") (name "/PUSHBUTTON") (class "Default")
      (node (ref "2560_PORTJ_LSA4") (pin "8") (pinfunction "S_8") (pintype "passive"))
      (node (ref "S1") (pin "2") (pinfunction "P_2") (pintype "passive"))
      (node (ref "S1") (pin "5") (pinfunction "P1_5") (pintype "passive"))
    )
    (net (code "77") (name "/R1") (class "Default")
      (node (ref "LED1") (pin "K") (pinfunction "C_K") (pintype "passive"))
      (node (ref "RN1") (pin "2") (pinfunction "2_2") (pintype "passive"))
    )
    (net (code "78") (name "/R2") (class "Default")
      (node (ref "LED2") (pin "K") (pinfunction "C_K") (pintype "passive"))
      (node (ref "RN1") (pin "3") (pinfunction "3_3") (pintype "passive"))
    )
    (net (code "79") (name "/R3") (class "Default")
      (node (ref "LED3") (pin "K") (pinfunction "C_K") (pintype "passive"))
      (node (ref "RN1") (pin "4") (pinfunction "4_4") (pintype "passive"))
    )
    (net (code "80") (name "/R4") (class "Default")
      (node (ref "LED4") (pin "K") (pinfunction "C_K") (pintype "passive"))
      (node (ref "RN1") (pin "5") (pinfunction "5_5") (pintype "passive"))
    )
    (net (code "81") (name "/R5") (class "Default")
      (node (ref "LED5") (pin "K") (pinfunction "C_K") (pintype "passive"))
      (node (ref "RN1") (pin "6") (pinfunction "6_6") (pintype "passive"))
    )
    (net (code "82") (name "/R6") (class "Default")
      (node (ref "LED6") (pin "K") (pinfunction "C_K") (pintype "passive"))
      (node (ref "RN1") (pin "7") (pinfunction "7_7") (pintype "passive"))
    )
    (net (code "83") (name "/R7") (class "Default")
      (node (ref "LED7") (pin "K") (pinfunction "C_K") (pintype "passive"))
      (node (ref "RN1") (pin "8") (pinfunction "8_8") (pintype "passive"))
    )
    (net (code "84") (name "/R8") (class "Default")
      (node (ref "LED8") (pin "K") (pinfunction "C_K") (pintype "passive"))
      (node (ref "RN1") (pin "9") (pinfunction "9_9") (pintype "passive"))
    )
    (net (code "85") (name "/RGB_5V") (class "Default")
      (node (ref "2560_PORTL") (pin "9") (pinfunction "S_9") (pintype "passive"))
      (node (ref "RGB-SIDE2") (pin "1") (pinfunction "S_1") (pintype "passive"))
    )
    (net (code "86") (name "/RX_PORTD") (class "Default")
      (node (ref "2560_PORTD_LSA2") (pin "3") (pinfunction "S_3") (pintype "passive"))
      (node (ref "LSA-2") (pin "1") (pinfunction "S_1") (pintype "passive"))
    )
    (net (code "87") (name "/RX_PORTE") (class "Default")
      (node (ref "2560_PORTE_LSA1") (pin "1") (pinfunction "S_1") (pintype "passive"))
      (node (ref "LSA-1") (pin "1") (pinfunction "S_1") (pintype "passive"))
    )
    (net (code "88") (name "/RX_PORTH") (class "Default")
      (node (ref "2560_PORTH_LSA3") (pin "1") (pinfunction "S_1") (pintype "passive"))
      (node (ref "LSA-3") (pin "1") (pinfunction "S_1") (pintype "passive"))
    )
    (net (code "89") (name "/RX_PORTJ") (class "Default")
      (node (ref "2560_PORTJ_LSA4") (pin "1") (pinfunction "S_1") (pintype "passive"))
      (node (ref "LSA-4") (pin "1") (pinfunction "S_1") (pintype "passive"))
    )
    (net (code "90") (name "/SCK") (class "Default")
      (node (ref "2560_PORTB") (pin "2") (pinfunction "S_2") (pintype "passive"))
      (node (ref "32_1_PORTB") (pin "8") (pinfunction "S_8") (pintype "passive"))
      (node (ref "32_2_PORTB") (pin "8") (pinfunction "S_8") (pintype "passive"))
      (node (ref "32_3_PORTB") (pin "8") (pinfunction "S_8") (pintype "passive"))
      (node (ref "32_4_PORTB") (pin "8") (pinfunction "S_8") (pintype "passive"))
    )
    (net (code "91") (name "/SHARP_5V") (class "Default")
      (node (ref "2560_PORTF") (pin "9") (pinfunction "S_9") (pintype "passive"))
      (node (ref "SHARP-1") (pin "1") (pinfunction "S_1") (pintype "passive"))
      (node (ref "SHARP-2") (pin "1") (pinfunction "S_1") (pintype "passive"))
    )
    (net (code "92") (name "/SHARP_ADC1") (class "Default")
      (node (ref "2560_PORTF") (pin "1") (pinfunction "S_1") (pintype "passive"))
      (node (ref "SHARP-1") (pin "2") (pinfunction "S_2") (pintype "passive"))
    )
    (net (code "93") (name "/SHARP_ADC2") (class "Default")
      (node (ref "2560_PORTF") (pin "2") (pinfunction "S_2") (pintype "passive"))
      (node (ref "SHARP-2") (pin "2") (pinfunction "S_2") (pintype "passive"))
    )
    (net (code "94") (name "/SS") (class "Default")
      (node (ref "2560_PORTB") (pin "1") (pinfunction "S_1") (pintype "passive"))
      (node (ref "32_1_PORTB") (pin "5") (pinfunction "S_5") (pintype "passive"))
      (node (ref "32_2_PORTB") (pin "5") (pinfunction "S_5") (pintype "passive"))
      (node (ref "32_3_PORTB") (pin "5") (pinfunction "S_5") (pintype "passive"))
      (node (ref "32_4_PORTB") (pin "5") (pinfunction "S_5") (pintype "passive"))
      (node (ref "R3") (pin "1") (pinfunction "1_1") (pintype "passive"))
      (node (ref "R4") (pin "1") (pinfunction "1_1") (pintype "passive"))
    )
    (net (code "95") (name "/T4") (class "Default")
      (node (ref "2560_ENC1") (pin "2") (pinfunction "S_2") (pintype "passive"))
      (node (ref "2560_PORTH_LSA3") (pin "8") (pinfunction "S_8") (pintype "passive"))
    )
    (net (code "96") (name "/T5") (class "Default")
      (node (ref "2560_ENC2") (pin "2") (pinfunction "S_2") (pintype "passive"))
      (node (ref "2560_PORTL") (pin "3") (pinfunction "S_3") (pintype "passive"))
      (node (ref "RGB-SIDE2") (pin "2") (pinfunction "S_2") (pintype "passive"))
    )
    (net (code "97") (name "/TX_PORTD") (class "Default")
      (node (ref "2560_PORTD_LSA2") (pin "4") (pinfunction "S_4") (pintype "passive"))
      (node (ref "LSA-2") (pin "2") (pinfunction "S_2") (pintype "passive"))
    )
    (net (code "98") (name "/TX_PORTE") (class "Default")
      (node (ref "2560_PORTE_LSA1") (pin "2") (pinfunction "S_2") (pintype "passive"))
      (node (ref "LSA-1") (pin "2") (pinfunction "S_2") (pintype "passive"))
    )
    (net (code "99") (name "/TX_PORTH") (class "Default")
      (node (ref "2560_PORTH_LSA3") (pin "2") (pinfunction "S_2") (pintype "passive"))
      (node (ref "LSA-3") (pin "2") (pinfunction "S_2") (pintype "passive"))
    )
    (net (code "100") (name "/TX_PORTJ") (class "Default")
      (node (ref "2560_PORTJ_LSA4") (pin "2") (pinfunction "S_2") (pintype "passive"))
      (node (ref "LSA-4") (pin "2") (pinfunction "S_2") (pintype "passive"))
    )
    (net (code "101") (name "Net-(LED18-PadA)") (class "Default")
      (node (ref "LED18") (pin "A") (pinfunction "A_A") (pintype "passive"))
      (node (ref "R2") (pin "2") (pinfunction "2_2") (pintype "passive"))
    )
    (net (code "102") (name "Net-(LED_PORTJ-S)") (class "Default")
      (node (ref "LED_PORT") (pin "9") (pinfunction "S_9") (pintype "passive"))
      (node (ref "R2") (pin "1") (pinfunction "1_1") (pintype "passive"))
    )
    (net (code "103") (name "unconnected-(32_1_PORTBB-S-Pad10)") (class "Default")
      (node (ref "32_1_PORTB") (pin "10") (pinfunction "S_10") (pintype "passive"))
    )
    (net (code "104") (name "unconnected-(32_1_PORTBC-S-Pad2)") (class "Default")
      (node (ref "32_1_PORTB") (pin "2") (pinfunction "S_2") (pintype "passive"))
    )
    (net (code "105") (name "unconnected-(32_1_PORTBD-S-Pad3)") (class "Default")
      (node (ref "32_1_PORTB") (pin "3") (pinfunction "S_3") (pintype "passive"))
    )
    (net (code "106") (name "unconnected-(32_1_PORTBE-S-Pad4)") (class "Default")
      (node (ref "32_1_PORTB") (pin "4") (pinfunction "S_4") (pintype "passive"))
    )
    (net (code "107") (name "unconnected-(32_1_PORTCB-S-Pad10)") (class "Default")
      (node (ref "32_1_PORTC") (pin "10") (pinfunction "S_10") (pintype "passive"))
    )
    (net (code "108") (name "unconnected-(32_1_PORTCC-S-Pad2)") (class "Default")
      (node (ref "32_1_PORTC") (pin "2") (pinfunction "S_2") (pintype "passive"))
    )
    (net (code "109") (name "unconnected-(32_1_PORTCD-S-Pad3)") (class "Default")
      (node (ref "32_1_PORTC") (pin "3") (pinfunction "S_3") (pintype "passive"))
    )
    (net (code "110") (name "unconnected-(32_1_PORTCE-S-Pad4)") (class "Default")
      (node (ref "32_1_PORTC") (pin "4") (pinfunction "S_4") (pintype "passive"))
    )
    (net (code "111") (name "unconnected-(32_1_PORTCF-S-Pad5)") (class "Default")
      (node (ref "32_1_PORTC") (pin "5") (pinfunction "S_5") (pintype "passive"))
    )
    (net (code "112") (name "unconnected-(32_1_PORTCG-S-Pad6)") (class "Default")
      (node (ref "32_1_PORTC") (pin "6") (pinfunction "S_6") (pintype "passive"))
    )
    (net (code "113") (name "unconnected-(32_1_PORTCH-S-Pad7)") (class "Default")
      (node (ref "32_1_PORTC") (pin "7") (pinfunction "S_7") (pintype "passive"))
    )
    (net (code "114") (name "unconnected-(32_1_PORTCI-S-Pad8)") (class "Default")
      (node (ref "32_1_PORTC") (pin "8") (pinfunction "S_8") (pintype "passive"))
    )
    (net (code "115") (name "unconnected-(32_1_PORTDD-S-Pad3)") (class "Default")
      (node (ref "32_1_PORTD") (pin "3") (pinfunction "S_3") (pintype "passive"))
    )
    (net (code "116") (name "unconnected-(32_1_PORTDE-S-Pad4)") (class "Default")
      (node (ref "32_1_PORTD") (pin "4") (pinfunction "S_4") (pintype "passive"))
    )
    (net (code "117") (name "unconnected-(32_1_PORTDF-S-Pad5)") (class "Default")
      (node (ref "32_1_PORTD") (pin "5") (pinfunction "S_5") (pintype "passive"))
    )
    (net (code "118") (name "unconnected-(32_1_PORTDH-S-Pad7)") (class "Default")
      (node (ref "32_1_PORTD") (pin "7") (pinfunction "S_7") (pintype "passive"))
    )
    (net (code "119") (name "unconnected-(32_1_PORTDI-S-Pad8)") (class "Default")
      (node (ref "32_1_PORTD") (pin "8") (pinfunction "S_8") (pintype "passive"))
    )
    (net (code "120") (name "unconnected-(32_2_PORTBC-S-Pad2)") (class "Default")
      (node (ref "32_2_PORTB") (pin "2") (pinfunction "S_2") (pintype "passive"))
    )
    (net (code "121") (name "unconnected-(32_2_PORTBD-S-Pad3)") (class "Default")
      (node (ref "32_2_PORTB") (pin "3") (pinfunction "S_3") (pintype "passive"))
    )
    (net (code "122") (name "unconnected-(32_2_PORTBE-S-Pad4)") (class "Default")
      (node (ref "32_2_PORTB") (pin "4") (pinfunction "S_4") (pintype "passive"))
    )
    (net (code "123") (name "unconnected-(32_2_PORTCB-S-Pad10)") (class "Default")
      (node (ref "32_2_PORTC") (pin "10") (pinfunction "S_10") (pintype "passive"))
    )
    (net (code "124") (name "unconnected-(32_2_PORTCC-S-Pad2)") (class "Default")
      (node (ref "32_2_PORTC") (pin "2") (pinfunction "S_2") (pintype "passive"))
    )
    (net (code "125") (name "unconnected-(32_2_PORTCD-S-Pad3)") (class "Default")
      (node (ref "32_2_PORTC") (pin "3") (pinfunction "S_3") (pintype "passive"))
    )
    (net (code "126") (name "unconnected-(32_2_PORTCE-S-Pad4)") (class "Default")
      (node (ref "32_2_PORTC") (pin "4") (pinfunction "S_4") (pintype "passive"))
    )
    (net (code "127") (name "unconnected-(32_2_PORTCF-S-Pad5)") (class "Default")
      (node (ref "32_2_PORTC") (pin "5") (pinfunction "S_5") (pintype "passive"))
    )
    (net (code "128") (name "unconnected-(32_2_PORTCG-S-Pad6)") (class "Default")
      (node (ref "32_2_PORTC") (pin "6") (pinfunction "S_6") (pintype "passive"))
    )
    (net (code "129") (name "unconnected-(32_2_PORTCH-S-Pad7)") (class "Default")
      (node (ref "32_2_PORTC") (pin "7") (pinfunction "S_7") (pintype "passive"))
    )
    (net (code "130") (name "unconnected-(32_2_PORTCI-S-Pad8)") (class "Default")
      (node (ref "32_2_PORTC") (pin "8") (pinfunction "S_8") (pintype "passive"))
    )
    (net (code "131") (name "unconnected-(32_2_PORTDD-S-Pad3)") (class "Default")
      (node (ref "32_2_PORTD") (pin "3") (pinfunction "S_3") (pintype "passive"))
    )
    (net (code "132") (name "unconnected-(32_2_PORTDE-S-Pad4)") (class "Default")
      (node (ref "32_2_PORTD") (pin "4") (pinfunction "S_4") (pintype "passive"))
    )
    (net (code "133") (name "unconnected-(32_2_PORTDF-S-Pad5)") (class "Default")
      (node (ref "32_2_PORTD") (pin "5") (pinfunction "S_5") (pintype "passive"))
    )
    (net (code "134") (name "unconnected-(32_2_PORTDH-S-Pad7)") (class "Default")
      (node (ref "32_2_PORTD") (pin "7") (pinfunction "S_7") (pintype "passive"))
    )
    (net (code "135") (name "unconnected-(32_2_PORTDI-S-Pad8)") (class "Default")
      (node (ref "32_2_PORTD") (pin "8") (pinfunction "S_8") (pintype "passive"))
    )
    (net (code "136") (name "unconnected-(32_3_PORTBB-S-Pad10)") (class "Default")
      (node (ref "32_3_PORTB") (pin "10") (pinfunction "S_10") (pintype "passive"))
    )
    (net (code "137") (name "unconnected-(32_3_PORTBC-S-Pad2)") (class "Default")
      (node (ref "32_3_PORTB") (pin "2") (pinfunction "S_2") (pintype "passive"))
    )
    (net (code "138") (name "unconnected-(32_3_PORTBD-S-Pad3)") (class "Default")
      (node (ref "32_3_PORTB") (pin "3") (pinfunction "S_3") (pintype "passive"))
    )
    (net (code "139") (name "unconnected-(32_3_PORTBE-S-Pad4)") (class "Default")
      (node (ref "32_3_PORTB") (pin "4") (pinfunction "S_4") (pintype "passive"))
    )
    (net (code "140") (name "unconnected-(32_3_PORTDD-S-Pad3)") (class "Default")
      (node (ref "32_3_PORTD") (pin "3") (pinfunction "S_3") (pintype "passive"))
    )
    (net (code "141") (name "unconnected-(32_3_PORTDE-S-Pad4)") (class "Default")
      (node (ref "32_3_PORTD") (pin "4") (pinfunction "S_4") (pintype "passive"))
    )
    (net (code "142") (name "unconnected-(32_3_PORTDF-S-Pad5)") (class "Default")
      (node (ref "32_3_PORTD") (pin "5") (pinfunction "S_5") (pintype "passive"))
    )
    (net (code "143") (name "unconnected-(32_3_PORTDH-S-Pad7)") (class "Default")
      (node (ref "32_3_PORTD") (pin "7") (pinfunction "S_7") (pintype "passive"))
    )
    (net (code "144") (name "unconnected-(32_3_PORTDI-S-Pad8)") (class "Default")
      (node (ref "32_3_PORTD") (pin "8") (pinfunction "S_8") (pintype "passive"))
    )
    (net (code "145") (name "unconnected-(32_4_PORTBB-S-Pad10)") (class "Default")
      (node (ref "32_4_PORTB") (pin "10") (pinfunction "S_10") (pintype "passive"))
    )
    (net (code "146") (name "unconnected-(32_4_PORTBC-S-Pad2)") (class "Default")
      (node (ref "32_4_PORTB") (pin "2") (pinfunction "S_2") (pintype "passive"))
    )
    (net (code "147") (name "unconnected-(32_4_PORTBD-S-Pad3)") (class "Default")
      (node (ref "32_4_PORTB") (pin "3") (pinfunction "S_3") (pintype "passive"))
    )
    (net (code "148") (name "unconnected-(32_4_PORTBE-S-Pad4)") (class "Default")
      (node (ref "32_4_PORTB") (pin "4") (pinfunction "S_4") (pintype "passive"))
    )
    (net (code "149") (name "unconnected-(32_4_PORTDD-S-Pad3)") (class "Default")
      (node (ref "32_4_PORTD") (pin "3") (pinfunction "S_3") (pintype "passive"))
    )
    (net (code "150") (name "unconnected-(32_4_PORTDE-S-Pad4)") (class "Default")
      (node (ref "32_4_PORTD") (pin "4") (pinfunction "S_4") (pintype "passive"))
    )
    (net (code "151") (name "unconnected-(32_4_PORTDF-S-Pad5)") (class "Default")
      (node (ref "32_4_PORTD") (pin "5") (pinfunction "S_5") (pintype "passive"))
    )
    (net (code "152") (name "unconnected-(32_4_PORTDH-S-Pad7)") (class "Default")
      (node (ref "32_4_PORTD") (pin "7") (pinfunction "S_7") (pintype "passive"))
    )
    (net (code "153") (name "unconnected-(32_4_PORTDI-S-Pad8)") (class "Default")
      (node (ref "32_4_PORTD") (pin "8") (pinfunction "S_8") (pintype "passive"))
    )
    (net (code "154") (name "unconnected-(2560_PORTBJ-S-Pad9)") (class "Default")
      (node (ref "2560_PORTB") (pin "9") (pinfunction "S_9") (pintype "passive"))
    )
    (net (code "155") (name "unconnected-(2560_PORTFD-S-Pad3)") (class "Default")
      (node (ref "2560_PORTF") (pin "3") (pinfunction "S_3") (pintype "passive"))
    )
    (net (code "156") (name "unconnected-(2560_PORTFE-S-Pad4)") (class "Default")
      (node (ref "2560_PORTF") (pin "4") (pinfunction "S_4") (pintype "passive"))
    )
    (net (code "157") (name "unconnected-(2560_PORTFF-S-Pad5)") (class "Default")
      (node (ref "2560_PORTF") (pin "5") (pinfunction "S_5") (pintype "passive"))
    )
    (net (code "158") (name "unconnected-(2560_PORTFG-S-Pad6)") (class "Default")
      (node (ref "2560_PORTF") (pin "6") (pinfunction "S_6") (pintype "passive"))
    )
    (net (code "159") (name "unconnected-(2560_PORTFH-S-Pad7)") (class "Default")
      (node (ref "2560_PORTF") (pin "7") (pinfunction "S_7") (pintype "passive"))
    )
    (net (code "160") (name "unconnected-(2560_PORTFI-S-Pad8)") (class "Default")
      (node (ref "2560_PORTF") (pin "8") (pinfunction "S_8") (pintype "passive"))
    )
    (net (code "161") (name "unconnected-(2560_PORTJ-S-Pad9)") (class "Default")
      (node (ref "2560_PORT") (pin "9") (pinfunction "S_9") (pintype "passive"))
    )
    (net (code "162") (name "unconnected-(LSA-1E-S-Pad4)") (class "Default")
      (node (ref "LSA-1") (pin "4") (pinfunction "S_4") (pintype "passive"))
    )
    (net (code "163") (name "unconnected-(LSA-1G-S-Pad6)") (class "Default")
      (node (ref "LSA-1") (pin "6") (pinfunction "S_6") (pintype "passive"))
    )
    (net (code "164") (name "unconnected-(LSA-1H-S-Pad7)") (class "Default")
      (node (ref "LSA-1") (pin "7") (pinfunction "S_7") (pintype "passive"))
    )
    (net (code "165") (name "unconnected-(LSA-1I-S-Pad8)") (class "Default")
      (node (ref "LSA-1") (pin "8") (pinfunction "S_8") (pintype "passive"))
    )
    (net (code "166") (name "unconnected-(LSA-2E-S-Pad4)") (class "Default")
      (node (ref "LSA-2") (pin "4") (pinfunction "S_4") (pintype "passive"))
    )
    (net (code "167") (name "unconnected-(LSA-2G-S-Pad6)") (class "Default")
      (node (ref "LSA-2") (pin "6") (pinfunction "S_6") (pintype "passive"))
    )
    (net (code "168") (name "unconnected-(LSA-2H-S-Pad7)") (class "Default")
      (node (ref "LSA-2") (pin "7") (pinfunction "S_7") (pintype "passive"))
    )
    (net (code "169") (name "unconnected-(LSA-2I-S-Pad8)") (class "Default")
      (node (ref "LSA-2") (pin "8") (pinfunction "S_8") (pintype "passive"))
    )
    (net (code "170") (name "unconnected-(LSA-3E-S-Pad4)") (class "Default")
      (node (ref "LSA-3") (pin "4") (pinfunction "S_4") (pintype "passive"))
    )
    (net (code "171") (name "unconnected-(LSA-3G-S-Pad6)") (class "Default")
      (node (ref "LSA-3") (pin "6") (pinfunction "S_6") (pintype "passive"))
    )
    (net (code "172") (name "unconnected-(LSA-3H-S-Pad7)") (class "Default")
      (node (ref "LSA-3") (pin "7") (pinfunction "S_7") (pintype "passive"))
    )
    (net (code "173") (name "unconnected-(LSA-3I-S-Pad8)") (class "Default")
      (node (ref "LSA-3") (pin "8") (pinfunction "S_8") (pintype "passive"))
    )
    (net (code "174") (name "unconnected-(LSA-4E-S-Pad4)") (class "Default")
      (node (ref "LSA-4") (pin "4") (pinfunction "S_4") (pintype "passive"))
    )
    (net (code "175") (name "unconnected-(LSA-4G-S-Pad6)") (class "Default")
      (node (ref "LSA-4") (pin "6") (pinfunction "S_6") (pintype "passive"))
    )
    (net (code "176") (name "unconnected-(LSA-4H-S-Pad7)") (class "Default")
      (node (ref "LSA-4") (pin "7") (pinfunction "S_7") (pintype "passive"))
    )
    (net (code "177") (name "unconnected-(LSA-4I-S-Pad8)") (class "Default")
      (node (ref "LSA-4") (pin "8") (pinfunction "S_8") (pintype "passive"))
    )
    (net (code "178") (name "unconnected-(MD1D-S-Pad4)") (class "Default")
      (node (ref "MD1") (pin "4") (pinfunction "S_4") (pintype "passive"))
    )
    (net (code "179") (name "unconnected-(MD1E-S-Pad5)") (class "Default")
      (node (ref "MD1") (pin "5") (pinfunction "S_5") (pintype "passive"))
    )
    (net (code "180") (name "unconnected-(MD2D-S-Pad4)") (class "Default")
      (node (ref "MD2") (pin "4") (pinfunction "S_4") (pintype "passive"))
    )
    (net (code "181") (name "unconnected-(MD2E-S-Pad5)") (class "Default")
      (node (ref "MD2") (pin "5") (pinfunction "S_5") (pintype "passive"))
    )
    (net (code "182") (name "unconnected-(MD3D-S-Pad4)") (class "Default")
      (node (ref "MD3") (pin "4") (pinfunction "S_4") (pintype "passive"))
    )
    (net (code "183") (name "unconnected-(MD3E-S-Pad5)") (class "Default")
      (node (ref "MD3") (pin "5") (pinfunction "S_5") (pintype "passive"))
    )
    (net (code "184") (name "unconnected-(MD4D-S-Pad4)") (class "Default")
      (node (ref "MD4") (pin "4") (pinfunction "S_4") (pintype "passive"))
    )
    (net (code "185") (name "unconnected-(MD4E-S-Pad5)") (class "Default")
      (node (ref "MD4") (pin "5") (pinfunction "S_5") (pintype "passive"))
    )
    (net (code "186") (name "unconnected-(MD5D-S-Pad4)") (class "Default")
      (node (ref "MD5") (pin "4") (pinfunction "S_4") (pintype "passive"))
    )
    (net (code "187") (name "unconnected-(MD5E-S-Pad5)") (class "Default")
      (node (ref "MD5") (pin "5") (pinfunction "S_5") (pintype "passive"))
    )
    (net (code "188") (name "unconnected-(MD6D-S-Pad4)") (class "Default")
      (node (ref "MD6") (pin "4") (pinfunction "S_4") (pintype "passive"))
    )
    (net (code "189") (name "unconnected-(MD6E-S-Pad5)") (class "Default")
      (node (ref "MD6") (pin "5") (pinfunction "S_5") (pintype "passive"))
    )
    (net (code "190") (name "unconnected-(MOTOR1D-S-Pad4)") (class "Default")
      (node (ref "MOTOR1") (pin "4") (pinfunction "S_4") (pintype "passive"))
    )
    (net (code "191") (name "unconnected-(MOTOR1E-S-Pad5)") (class "Default")
      (node (ref "MOTOR1") (pin "5") (pinfunction "S_5") (pintype "passive"))
    )
    (net (code "192") (name "unconnected-(MOTOR2D-S-Pad4)") (class "Default")
      (node (ref "MOTOR2") (pin "4") (pinfunction "S_4") (pintype "passive"))
    )
    (net (code "193") (name "unconnected-(MOTOR2E-S-Pad5)") (class "Default")
      (node (ref "MOTOR2") (pin "5") (pinfunction "S_5") (pintype "passive"))
    )
    (net (code "194") (name "unconnected-(MOTOR3D-S-Pad4)") (class "Default")
      (node (ref "MOTOR3") (pin "4") (pinfunction "S_4") (pintype "passive"))
    )
    (net (code "195") (name "unconnected-(MOTOR3E-S-Pad5)") (class "Default")
      (node (ref "MOTOR3") (pin "5") (pinfunction "S_5") (pintype "passive"))
    )
    (net (code "196") (name "unconnected-(MOTORR4D-S-Pad4)") (class "Default")
      (node (ref "MOTORR4") (pin "4") (pinfunction "S_4") (pintype "passive"))
    )
    (net (code "197") (name "unconnected-(MOTORR4E-S-Pad5)") (class "Default")
      (node (ref "MOTORR4") (pin "5") (pinfunction "S_5") (pintype "passive"))
    )
    (net (code "198") (name "unconnected-(NANOD-S-Pad4)") (class "Default")
      (node (ref "NANO") (pin "4") (pinfunction "S_4") (pintype "passive"))
    )
    (net (code "199") (name "unconnected-(S1-O-Pad1)") (class "Default")
      (node (ref "S1") (pin "1") (pinfunction "O_1") (pintype "passive"))
    )
    (net (code "200") (name "unconnected-(S1-S1-Pad6)") (class "Default")
      (node (ref "S1") (pin "6") (pinfunction "S1_6") (pintype "passive"))
    )
  )
)
